# knitic_v2_1.net
KiCad netlist of a schematic drawn in EAGLE
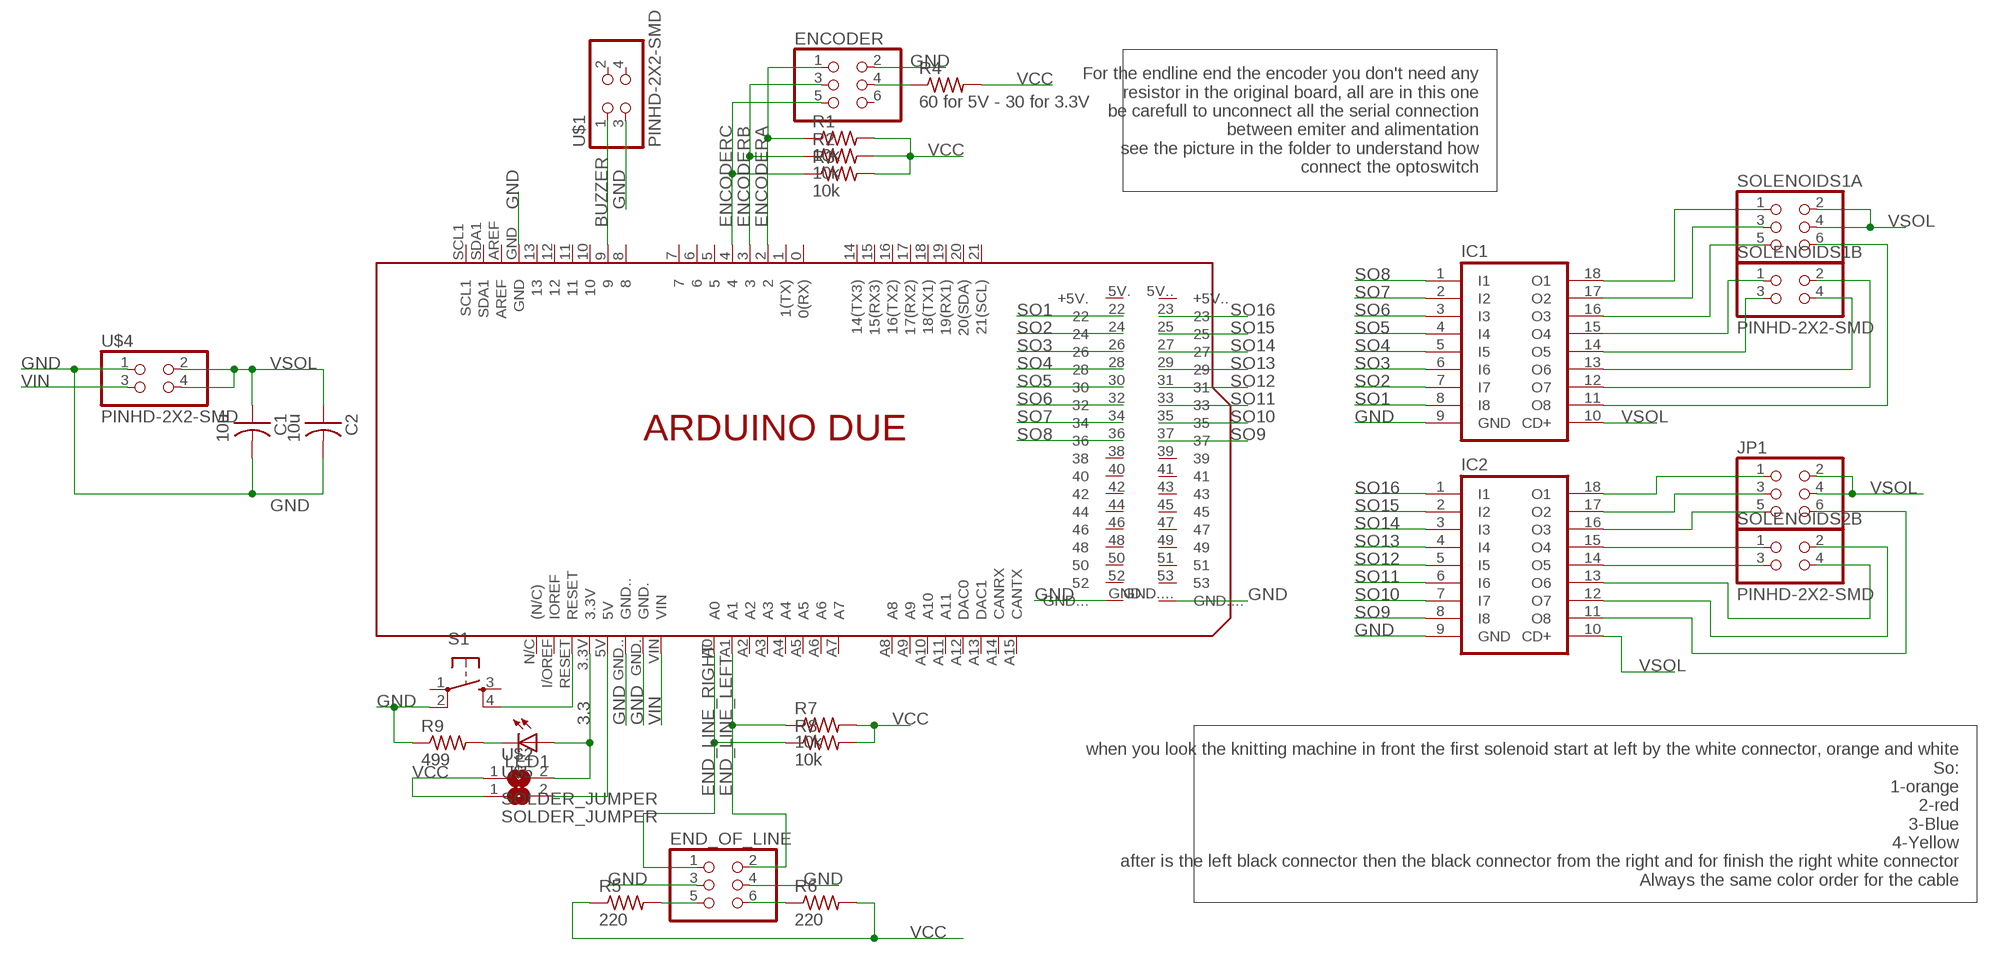
[diagram p0: schematic, sheet 1]

(export (version "E")
  (design (tool "Eeschema 10.0.6"))
  (components
    (comp (ref "C1")
      (value "10u")
      (footprint "eagle-import:C1206FAB")
      (libsource (lib "eagle-import") (part "CAP-US1206FAB"))
    )
    (comp (ref "C2")
      (value "10u")
      (footprint "eagle-import:C1206FAB")
      (libsource (lib "eagle-import") (part "CAP-US1206FAB"))
    )
    (comp (ref "ENCODER")
      (value "PINHD-2X3-SMD")
      (footprint "eagle-import:2X03SMD")
      (libsource (lib "eagle-import") (part "PINHD-2X3-SMD"))
    )
    (comp (ref "END_OF_LINE")
      (value "PINHD-2X3-SMD")
      (footprint "eagle-import:2X03SMD")
      (libsource (lib "eagle-import") (part "PINHD-2X3-SMD"))
    )
    (comp (ref "IC1")
      (value "ULN2803ASO")
      (footprint "eagle-import:SO18W")
      (libsource (lib "eagle-import") (part "ULN2803ASO"))
    )
    (comp (ref "IC2")
      (value "ULN2803ASO")
      (footprint "eagle-import:SO18W")
      (libsource (lib "eagle-import") (part "ULN2803ASO"))
    )
    (comp (ref "JP1")
      (value "PINHD-2X3-SMD")
      (footprint "eagle-import:2X03SMD")
      (libsource (lib "eagle-import") (part "PINHD-2X3-SMD"))
    )
    (comp (ref "LED1")
      (value "LEDSMT1206")
      (footprint "eagle-import:1206")
      (libsource (lib "eagle-import") (part "LEDSMT1206"))
    )
    (comp (ref "PCB1")
      (value "ARDUINO_DUE_MIN")
      (footprint "eagle-import:ARDUINO_DUE_MIN")
      (libsource (lib "eagle-import") (part "ARDUINO_DUE_MIN"))
    )
    (comp (ref "R1")
      (value "10k")
      (footprint "eagle-import:R1206FAB")
      (libsource (lib "eagle-import") (part "RES-US1206FAB"))
    )
    (comp (ref "R2")
      (value "10k")
      (footprint "eagle-import:R1206FAB")
      (libsource (lib "eagle-import") (part "RES-US1206FAB"))
    )
    (comp (ref "R3")
      (value "10k")
      (footprint "eagle-import:R1206FAB")
      (libsource (lib "eagle-import") (part "RES-US1206FAB"))
    )
    (comp (ref "R4")
      (value "60 for 5V - 30 for 3.3V")
      (footprint "eagle-import:R1206FAB")
      (libsource (lib "eagle-import") (part "RES-US1206FAB"))
    )
    (comp (ref "R5")
      (value "220")
      (footprint "eagle-import:R1206FAB")
      (libsource (lib "eagle-import") (part "RES-US1206FAB"))
    )
    (comp (ref "R6")
      (value "220")
      (footprint "eagle-import:R1206FAB")
      (libsource (lib "eagle-import") (part "RES-US1206FAB"))
    )
    (comp (ref "R7")
      (value "10k")
      (footprint "eagle-import:R1206FAB")
      (libsource (lib "eagle-import") (part "RES-US1206FAB"))
    )
    (comp (ref "R8")
      (value "10k")
      (footprint "eagle-import:R1206FAB")
      (libsource (lib "eagle-import") (part "RES-US1206FAB"))
    )
    (comp (ref "R9")
      (value "499")
      (footprint "eagle-import:R1206FAB")
      (libsource (lib "eagle-import") (part "RES-US1206FAB"))
    )
    (comp (ref "S1")
      (value "6MM_SWITCH6MM_SWITCH")
      (footprint "eagle-import:6MM_SWITCH")
      (libsource (lib "eagle-import") (part "6MM_SWITCH6MM_SWITCH"))
    )
    (comp (ref "SOLENOIDS1A")
      (value "PINHD-2X3-SMD")
      (footprint "eagle-import:2X03SMD")
      (libsource (lib "eagle-import") (part "PINHD-2X3-SMD"))
    )
    (comp (ref "SOLENOIDS1B")
      (value "PINHD-2X2-SMD")
      (footprint "eagle-import:2X02SMD")
      (libsource (lib "eagle-import") (part "PINHD-2X2-SMD"))
    )
    (comp (ref "SOLENOIDS2B")
      (value "PINHD-2X2-SMD")
      (footprint "eagle-import:2X02SMD")
      (libsource (lib "eagle-import") (part "PINHD-2X2-SMD"))
    )
    (comp (ref "U$1")
      (value "PINHD-2X2-SMD")
      (footprint "eagle-import:2X02SMD")
      (libsource (lib "eagle-import") (part "PINHD-2X2-SMD"))
    )
    (comp (ref "U$2")
      (value "SOLDER_JUMPER")
      (footprint "eagle-import:SJFAB")
      (libsource (lib "eagle-import") (part "SOLDER_JUMPER"))
    )
    (comp (ref "U$4")
      (value "PINHD-2X2-SMD")
      (footprint "eagle-import:2X02SMD")
      (libsource (lib "eagle-import") (part "PINHD-2X2-SMD"))
    )
    (comp (ref "U$5")
      (value "SOLDER_JUMPER")
      (footprint "eagle-import:SJFAB")
      (libsource (lib "eagle-import") (part "SOLDER_JUMPER"))
    )
  )
  (nets
    (net (code "1") (name "/3.3") (class "Default")
      (node (ref "LED1") (pin "A") (pinfunction "A_A") (pintype "passive"))
      (node (ref "PCB1") (pin "3.3V") (pinfunction "3.3V_3.3V") (pintype "bidirectional"))
      (node (ref "U$2") (pin "2") (pinfunction "2_2") (pintype "passive"))
    )
    (net (code "2") (name "/BUZZER") (class "Default")
      (node (ref "PCB1") (pin "9") (pinfunction "9_9") (pintype "bidirectional"))
      (node (ref "U$1") (pin "1") (pinfunction "1_1") (pintype "passive"))
    )
    (net (code "3") (name "/ENCODERA") (class "Default")
      (node (ref "ENCODER") (pin "1") (pinfunction "1_1") (pintype "passive"))
      (node (ref "PCB1") (pin "2") (pinfunction "2_2") (pintype "bidirectional"))
      (node (ref "R1") (pin "1") (pinfunction "1_1") (pintype "passive"))
    )
    (net (code "4") (name "/ENCODERB") (class "Default")
      (node (ref "ENCODER") (pin "3") (pinfunction "3_3") (pintype "passive"))
      (node (ref "PCB1") (pin "3") (pinfunction "3_3") (pintype "bidirectional"))
      (node (ref "R2") (pin "1") (pinfunction "1_1") (pintype "passive"))
    )
    (net (code "5") (name "/ENCODERC") (class "Default")
      (node (ref "ENCODER") (pin "5") (pinfunction "5_5") (pintype "passive"))
      (node (ref "PCB1") (pin "4") (pinfunction "4_4") (pintype "bidirectional"))
      (node (ref "R3") (pin "1") (pinfunction "1_1") (pintype "passive"))
    )
    (net (code "6") (name "/END_LINE_LEFT") (class "Default")
      (node (ref "END_OF_LINE") (pin "2") (pinfunction "2_2") (pintype "passive"))
      (node (ref "PCB1") (pin "A1") (pinfunction "A1_A1") (pintype "bidirectional"))
      (node (ref "R7") (pin "1") (pinfunction "1_1") (pintype "passive"))
    )
    (net (code "7") (name "/END_LINE_RIGHT") (class "Default")
      (node (ref "END_OF_LINE") (pin "1") (pinfunction "1_1") (pintype "passive"))
      (node (ref "PCB1") (pin "A0") (pinfunction "A0_A0") (pintype "bidirectional"))
      (node (ref "R8") (pin "1") (pinfunction "1_1") (pintype "passive"))
    )
    (net (code "8") (name "/GND") (class "Default")
      (node (ref "C1") (pin "2") (pinfunction "2_2") (pintype "passive"))
      (node (ref "C2") (pin "2") (pinfunction "2_2") (pintype "passive"))
      (node (ref "ENCODER") (pin "2") (pinfunction "2_2") (pintype "passive"))
      (node (ref "END_OF_LINE") (pin "3") (pinfunction "3_3") (pintype "passive"))
      (node (ref "END_OF_LINE") (pin "4") (pinfunction "4_4") (pintype "passive"))
      (node (ref "IC1") (pin "9") (pinfunction "GND_9") (pintype "power_in"))
      (node (ref "IC2") (pin "9") (pinfunction "GND_9") (pintype "power_in"))
      (node (ref "PCB1") (pin "GND") (pinfunction "GND_GND") (pintype "bidirectional"))
      (node (ref "PCB1") (pin "GND.") (pinfunction "GND._GND.") (pintype "bidirectional"))
      (node (ref "PCB1") (pin "GND..") (pinfunction "GND.._GND..") (pintype "bidirectional"))
      (node (ref "R9") (pin "1") (pinfunction "1_1") (pintype "passive"))
      (node (ref "S1") (pin "2") (pinfunction "P1_2") (pintype "passive"))
      (node (ref "U$1") (pin "3") (pinfunction "3_3") (pintype "passive"))
      (node (ref "U$4") (pin "1") (pinfunction "1_1") (pintype "passive"))
    )
    (net (code "9") (name "/SO1") (class "Default")
      (node (ref "IC1") (pin "8") (pinfunction "I8_8") (pintype "input"))
      (node (ref "PCB1") (pin "22") (pinfunction "22_22") (pintype "bidirectional"))
    )
    (net (code "10") (name "/SO2") (class "Default")
      (node (ref "IC1") (pin "7") (pinfunction "I7_7") (pintype "input"))
      (node (ref "PCB1") (pin "24") (pinfunction "24_24") (pintype "bidirectional"))
    )
    (net (code "11") (name "/SO3") (class "Default")
      (node (ref "IC1") (pin "6") (pinfunction "I6_6") (pintype "input"))
      (node (ref "PCB1") (pin "26") (pinfunction "26_26") (pintype "bidirectional"))
    )
    (net (code "12") (name "/SO4") (class "Default")
      (node (ref "IC1") (pin "5") (pinfunction "I5_5") (pintype "input"))
      (node (ref "PCB1") (pin "28") (pinfunction "28_28") (pintype "bidirectional"))
    )
    (net (code "13") (name "/SO5") (class "Default")
      (node (ref "IC1") (pin "4") (pinfunction "I4_4") (pintype "input"))
      (node (ref "PCB1") (pin "30") (pinfunction "30_30") (pintype "bidirectional"))
    )
    (net (code "14") (name "/SO6") (class "Default")
      (node (ref "IC1") (pin "3") (pinfunction "I3_3") (pintype "input"))
      (node (ref "PCB1") (pin "32") (pinfunction "32_32") (pintype "bidirectional"))
    )
    (net (code "15") (name "/SO7") (class "Default")
      (node (ref "IC1") (pin "2") (pinfunction "I2_2") (pintype "input"))
      (node (ref "PCB1") (pin "34") (pinfunction "34_34") (pintype "bidirectional"))
    )
    (net (code "16") (name "/SO8") (class "Default")
      (node (ref "IC1") (pin "1") (pinfunction "I1_1") (pintype "input"))
      (node (ref "PCB1") (pin "36") (pinfunction "36_36") (pintype "bidirectional"))
    )
    (net (code "17") (name "/SO9") (class "Default")
      (node (ref "IC2") (pin "8") (pinfunction "I8_8") (pintype "input"))
      (node (ref "PCB1") (pin "37") (pinfunction "37_37") (pintype "bidirectional"))
    )
    (net (code "18") (name "/SO10") (class "Default")
      (node (ref "IC2") (pin "7") (pinfunction "I7_7") (pintype "input"))
      (node (ref "PCB1") (pin "35") (pinfunction "35_35") (pintype "bidirectional"))
    )
    (net (code "19") (name "/SO11") (class "Default")
      (node (ref "IC2") (pin "6") (pinfunction "I6_6") (pintype "input"))
      (node (ref "PCB1") (pin "33") (pinfunction "33_33") (pintype "bidirectional"))
    )
    (net (code "20") (name "/SO12") (class "Default")
      (node (ref "IC2") (pin "5") (pinfunction "I5_5") (pintype "input"))
      (node (ref "PCB1") (pin "31") (pinfunction "31_31") (pintype "bidirectional"))
    )
    (net (code "21") (name "/SO13") (class "Default")
      (node (ref "IC2") (pin "4") (pinfunction "I4_4") (pintype "input"))
      (node (ref "PCB1") (pin "29") (pinfunction "29_29") (pintype "bidirectional"))
    )
    (net (code "22") (name "/SO14") (class "Default")
      (node (ref "IC2") (pin "3") (pinfunction "I3_3") (pintype "input"))
      (node (ref "PCB1") (pin "27") (pinfunction "27_27") (pintype "bidirectional"))
    )
    (net (code "23") (name "/SO15") (class "Default")
      (node (ref "IC2") (pin "2") (pinfunction "I2_2") (pintype "input"))
      (node (ref "PCB1") (pin "25") (pinfunction "25_25") (pintype "bidirectional"))
    )
    (net (code "24") (name "/SO16") (class "Default")
      (node (ref "IC2") (pin "1") (pinfunction "I1_1") (pintype "input"))
      (node (ref "PCB1") (pin "23") (pinfunction "23_23") (pintype "bidirectional"))
    )
    (net (code "25") (name "/VCC") (class "Default")
      (node (ref "R1") (pin "2") (pinfunction "2_2") (pintype "passive"))
      (node (ref "R2") (pin "2") (pinfunction "2_2") (pintype "passive"))
      (node (ref "R3") (pin "2") (pinfunction "2_2") (pintype "passive"))
      (node (ref "R4") (pin "2") (pinfunction "2_2") (pintype "passive"))
      (node (ref "R5") (pin "1") (pinfunction "1_1") (pintype "passive"))
      (node (ref "R6") (pin "2") (pinfunction "2_2") (pintype "passive"))
      (node (ref "R7") (pin "2") (pinfunction "2_2") (pintype "passive"))
      (node (ref "R8") (pin "2") (pinfunction "2_2") (pintype "passive"))
      (node (ref "U$2") (pin "1") (pinfunction "1_1") (pintype "passive"))
      (node (ref "U$5") (pin "1") (pinfunction "1_1") (pintype "passive"))
    )
    (net (code "26") (name "/VIN") (class "Default")
      (node (ref "PCB1") (pin "VIN") (pinfunction "VIN_VIN") (pintype "bidirectional"))
      (node (ref "U$4") (pin "3") (pinfunction "3_3") (pintype "passive"))
    )
    (net (code "27") (name "/VSOL") (class "Default")
      (node (ref "C1") (pin "1") (pinfunction "1_1") (pintype "passive"))
      (node (ref "C2") (pin "1") (pinfunction "1_1") (pintype "passive"))
      (node (ref "IC1") (pin "10") (pinfunction "CD+_10") (pintype "passive"))
      (node (ref "IC2") (pin "10") (pinfunction "CD+_10") (pintype "passive"))
      (node (ref "JP1") (pin "2") (pinfunction "2_2") (pintype "passive"))
      (node (ref "JP1") (pin "4") (pinfunction "4_4") (pintype "passive"))
      (node (ref "SOLENOIDS1A") (pin "2") (pinfunction "2_2") (pintype "passive"))
      (node (ref "SOLENOIDS1A") (pin "4") (pinfunction "4_4") (pintype "passive"))
      (node (ref "U$4") (pin "2") (pinfunction "2_2") (pintype "passive"))
      (node (ref "U$4") (pin "4") (pinfunction "4_4") (pintype "passive"))
    )
    (net (code "28") (name "Net-(ENCODER-Pad4)") (class "Default")
      (node (ref "ENCODER") (pin "4") (pinfunction "4_4") (pintype "passive"))
      (node (ref "R4") (pin "1") (pinfunction "1_1") (pintype "passive"))
    )
    (net (code "29") (name "Net-(END_OF_LINE-Pad5)") (class "Default")
      (node (ref "END_OF_LINE") (pin "5") (pinfunction "5_5") (pintype "passive"))
      (node (ref "R5") (pin "2") (pinfunction "2_2") (pintype "passive"))
    )
    (net (code "30") (name "Net-(END_OF_LINE-Pad6)") (class "Default")
      (node (ref "END_OF_LINE") (pin "6") (pinfunction "6_6") (pintype "passive"))
      (node (ref "R6") (pin "1") (pinfunction "1_1") (pintype "passive"))
    )
    (net (code "31") (name "Net-(IC1-O1)") (class "Default")
      (node (ref "IC1") (pin "18") (pinfunction "O1_18") (pintype "open_collector"))
      (node (ref "SOLENOIDS1A") (pin "1") (pinfunction "1_1") (pintype "passive"))
    )
    (net (code "32") (name "Net-(IC1-O2)") (class "Default")
      (node (ref "IC1") (pin "17") (pinfunction "O2_17") (pintype "open_collector"))
      (node (ref "SOLENOIDS1A") (pin "3") (pinfunction "3_3") (pintype "passive"))
    )
    (net (code "33") (name "Net-(IC1-O3)") (class "Default")
      (node (ref "IC1") (pin "16") (pinfunction "O3_16") (pintype "open_collector"))
      (node (ref "SOLENOIDS1A") (pin "5") (pinfunction "5_5") (pintype "passive"))
    )
    (net (code "34") (name "Net-(IC1-O4)") (class "Default")
      (node (ref "IC1") (pin "15") (pinfunction "O4_15") (pintype "open_collector"))
      (node (ref "SOLENOIDS1B") (pin "1") (pinfunction "1_1") (pintype "passive"))
    )
    (net (code "35") (name "Net-(IC1-O5)") (class "Default")
      (node (ref "IC1") (pin "14") (pinfunction "O5_14") (pintype "open_collector"))
      (node (ref "SOLENOIDS1B") (pin "3") (pinfunction "3_3") (pintype "passive"))
    )
    (net (code "36") (name "Net-(IC1-O6)") (class "Default")
      (node (ref "IC1") (pin "13") (pinfunction "O6_13") (pintype "open_collector"))
      (node (ref "SOLENOIDS1B") (pin "4") (pinfunction "4_4") (pintype "passive"))
    )
    (net (code "37") (name "Net-(IC1-O7)") (class "Default")
      (node (ref "IC1") (pin "12") (pinfunction "O7_12") (pintype "open_collector"))
      (node (ref "SOLENOIDS1B") (pin "2") (pinfunction "2_2") (pintype "passive"))
    )
    (net (code "38") (name "Net-(IC1-O8)") (class "Default")
      (node (ref "IC1") (pin "11") (pinfunction "O8_11") (pintype "open_collector"))
      (node (ref "SOLENOIDS1A") (pin "6") (pinfunction "6_6") (pintype "passive"))
    )
    (net (code "39") (name "Net-(IC2-O1)") (class "Default")
      (node (ref "IC2") (pin "18") (pinfunction "O1_18") (pintype "open_collector"))
      (node (ref "JP1") (pin "1") (pinfunction "1_1") (pintype "passive"))
    )
    (net (code "40") (name "Net-(IC2-O2)") (class "Default")
      (node (ref "IC2") (pin "17") (pinfunction "O2_17") (pintype "open_collector"))
      (node (ref "JP1") (pin "3") (pinfunction "3_3") (pintype "passive"))
    )
    (net (code "41") (name "Net-(IC2-O3)") (class "Default")
      (node (ref "IC2") (pin "16") (pinfunction "O3_16") (pintype "open_collector"))
      (node (ref "JP1") (pin "5") (pinfunction "5_5") (pintype "passive"))
    )
    (net (code "42") (name "Net-(IC2-O4)") (class "Default")
      (node (ref "IC2") (pin "15") (pinfunction "O4_15") (pintype "open_collector"))
      (node (ref "SOLENOIDS2B") (pin "1") (pinfunction "1_1") (pintype "passive"))
    )
    (net (code "43") (name "Net-(IC2-O5)") (class "Default")
      (node (ref "IC2") (pin "14") (pinfunction "O5_14") (pintype "open_collector"))
      (node (ref "SOLENOIDS2B") (pin "3") (pinfunction "3_3") (pintype "passive"))
    )
    (net (code "44") (name "Net-(IC2-O6)") (class "Default")
      (node (ref "IC2") (pin "13") (pinfunction "O6_13") (pintype "open_collector"))
      (node (ref "SOLENOIDS2B") (pin "4") (pinfunction "4_4") (pintype "passive"))
    )
    (net (code "45") (name "Net-(IC2-O7)") (class "Default")
      (node (ref "IC2") (pin "12") (pinfunction "O7_12") (pintype "open_collector"))
      (node (ref "SOLENOIDS2B") (pin "2") (pinfunction "2_2") (pintype "passive"))
    )
    (net (code "46") (name "Net-(IC2-O8)") (class "Default")
      (node (ref "IC2") (pin "11") (pinfunction "O8_11") (pintype "open_collector"))
      (node (ref "JP1") (pin "6") (pinfunction "6_6") (pintype "passive"))
    )
    (net (code "47") (name "Net-(LED1-PadC)") (class "Default")
      (node (ref "LED1") (pin "C") (pinfunction "C_C") (pintype "passive"))
      (node (ref "R9") (pin "2") (pinfunction "2_2") (pintype "passive"))
    )
    (net (code "48") (name "Net-(PCB1-Pad5V)") (class "Default")
      (node (ref "PCB1") (pin "5V") (pinfunction "5V_5V") (pintype "bidirectional"))
      (node (ref "U$5") (pin "2") (pinfunction "2_2") (pintype "passive"))
    )
    (net (code "49") (name "Net-(S1-S1)") (class "Default")
      (node (ref "PCB1") (pin "RESET") (pinfunction "RESET_RESET") (pintype "bidirectional"))
      (node (ref "S1") (pin "4") (pinfunction "S1_4") (pintype "passive"))
    )
    (net (code "50") (name "unconnected-(ENCODER-Pad6)") (class "Default")
      (node (ref "ENCODER") (pin "6") (pinfunction "6_6") (pintype "passive"))
    )
    (net (code "51") (name "unconnected-(PCB1-(N{slash}C)-PadN{slash}C)") (class "Default")
      (node (ref "PCB1") (pin "N/C") (pinfunction "(N/C)_N/C") (pintype "bidirectional"))
    )
    (net (code "52") (name "unconnected-(PCB1-+5V.-Pad5V.)") (class "Default")
      (node (ref "PCB1") (pin "5V.") (pinfunction "+5V._5V.") (pintype "bidirectional"))
    )
    (net (code "53") (name "unconnected-(PCB1-+5V..-Pad5V..)") (class "Default")
      (node (ref "PCB1") (pin "5V..") (pinfunction "+5V.._5V..") (pintype "bidirectional"))
    )
    (net (code "54") (name "unconnected-(PCB1-0(RX)-Pad0)") (class "Default")
      (node (ref "PCB1") (pin "0") (pinfunction "0(RX)_0") (pintype "bidirectional"))
    )
    (net (code "55") (name "unconnected-(PCB1-1(TX)-Pad1)") (class "Default")
      (node (ref "PCB1") (pin "1") (pinfunction "1(TX)_1") (pintype "bidirectional"))
    )
    (net (code "56") (name "unconnected-(PCB1-14(TX3)-Pad14)") (class "Default")
      (node (ref "PCB1") (pin "14") (pinfunction "14(TX3)_14") (pintype "bidirectional"))
    )
    (net (code "57") (name "unconnected-(PCB1-15(RX3)-Pad15)") (class "Default")
      (node (ref "PCB1") (pin "15") (pinfunction "15(RX3)_15") (pintype "bidirectional"))
    )
    (net (code "58") (name "unconnected-(PCB1-16(TX2)-Pad16)") (class "Default")
      (node (ref "PCB1") (pin "16") (pinfunction "16(TX2)_16") (pintype "bidirectional"))
    )
    (net (code "59") (name "unconnected-(PCB1-17(RX2)-Pad17)") (class "Default")
      (node (ref "PCB1") (pin "17") (pinfunction "17(RX2)_17") (pintype "bidirectional"))
    )
    (net (code "60") (name "unconnected-(PCB1-18(TX1)-Pad18)") (class "Default")
      (node (ref "PCB1") (pin "18") (pinfunction "18(TX1)_18") (pintype "bidirectional"))
    )
    (net (code "61") (name "unconnected-(PCB1-19(RX1)-Pad19)") (class "Default")
      (node (ref "PCB1") (pin "19") (pinfunction "19(RX1)_19") (pintype "bidirectional"))
    )
    (net (code "62") (name "unconnected-(PCB1-20(SDA)-Pad20)") (class "Default")
      (node (ref "PCB1") (pin "20") (pinfunction "20(SDA)_20") (pintype "bidirectional"))
    )
    (net (code "63") (name "unconnected-(PCB1-21(SCL)-Pad21)") (class "Default")
      (node (ref "PCB1") (pin "21") (pinfunction "21(SCL)_21") (pintype "bidirectional"))
    )
    (net (code "64") (name "unconnected-(PCB1-CANRX-PadA14)") (class "Default")
      (node (ref "PCB1") (pin "A14") (pinfunction "CANRX_A14") (pintype "bidirectional"))
    )
    (net (code "65") (name "unconnected-(PCB1-CANTX-PadA15)") (class "Default")
      (node (ref "PCB1") (pin "A15") (pinfunction "CANTX_A15") (pintype "bidirectional"))
    )
    (net (code "66") (name "unconnected-(PCB1-DAC0-PadA12)") (class "Default")
      (node (ref "PCB1") (pin "A12") (pinfunction "DAC0_A12") (pintype "bidirectional"))
    )
    (net (code "67") (name "unconnected-(PCB1-DAC1-PadA13)") (class "Default")
      (node (ref "PCB1") (pin "A13") (pinfunction "DAC1_A13") (pintype "bidirectional"))
    )
    (net (code "68") (name "unconnected-(PCB1-IOREF-PadI{slash}OREF)") (class "Default")
      (node (ref "PCB1") (pin "I/OREF") (pinfunction "IOREF_I/OREF") (pintype "bidirectional"))
    )
    (net (code "69") (name "unconnected-(PCB1-Pad5)") (class "Default")
      (node (ref "PCB1") (pin "5") (pinfunction "5_5") (pintype "bidirectional"))
    )
    (net (code "70") (name "unconnected-(PCB1-Pad6)") (class "Default")
      (node (ref "PCB1") (pin "6") (pinfunction "6_6") (pintype "bidirectional"))
    )
    (net (code "71") (name "unconnected-(PCB1-Pad7)") (class "Default")
      (node (ref "PCB1") (pin "7") (pinfunction "7_7") (pintype "bidirectional"))
    )
    (net (code "72") (name "unconnected-(PCB1-Pad8)") (class "Default")
      (node (ref "PCB1") (pin "8") (pinfunction "8_8") (pintype "bidirectional"))
    )
    (net (code "73") (name "unconnected-(PCB1-Pad10)") (class "Default")
      (node (ref "PCB1") (pin "10") (pinfunction "10_10") (pintype "bidirectional"))
    )
    (net (code "74") (name "unconnected-(PCB1-Pad11)") (class "Default")
      (node (ref "PCB1") (pin "11") (pinfunction "11_11") (pintype "bidirectional"))
    )
    (net (code "75") (name "unconnected-(PCB1-Pad12)") (class "Default")
      (node (ref "PCB1") (pin "12") (pinfunction "12_12") (pintype "bidirectional"))
    )
    (net (code "76") (name "unconnected-(PCB1-Pad13)") (class "Default")
      (node (ref "PCB1") (pin "13") (pinfunction "13_13") (pintype "bidirectional"))
    )
    (net (code "77") (name "unconnected-(PCB1-Pad38)") (class "Default")
      (node (ref "PCB1") (pin "38") (pinfunction "38_38") (pintype "bidirectional"))
    )
    (net (code "78") (name "unconnected-(PCB1-Pad39)") (class "Default")
      (node (ref "PCB1") (pin "39") (pinfunction "39_39") (pintype "bidirectional"))
    )
    (net (code "79") (name "unconnected-(PCB1-Pad40)") (class "Default")
      (node (ref "PCB1") (pin "40") (pinfunction "40_40") (pintype "bidirectional"))
    )
    (net (code "80") (name "unconnected-(PCB1-Pad41)") (class "Default")
      (node (ref "PCB1") (pin "41") (pinfunction "41_41") (pintype "bidirectional"))
    )
    (net (code "81") (name "unconnected-(PCB1-Pad42)") (class "Default")
      (node (ref "PCB1") (pin "42") (pinfunction "42_42") (pintype "bidirectional"))
    )
    (net (code "82") (name "unconnected-(PCB1-Pad43)") (class "Default")
      (node (ref "PCB1") (pin "43") (pinfunction "43_43") (pintype "bidirectional"))
    )
    (net (code "83") (name "unconnected-(PCB1-Pad44)") (class "Default")
      (node (ref "PCB1") (pin "44") (pinfunction "44_44") (pintype "bidirectional"))
    )
    (net (code "84") (name "unconnected-(PCB1-Pad45)") (class "Default")
      (node (ref "PCB1") (pin "45") (pinfunction "45_45") (pintype "bidirectional"))
    )
    (net (code "85") (name "unconnected-(PCB1-Pad46)") (class "Default")
      (node (ref "PCB1") (pin "46") (pinfunction "46_46") (pintype "bidirectional"))
    )
    (net (code "86") (name "unconnected-(PCB1-Pad47)") (class "Default")
      (node (ref "PCB1") (pin "47") (pinfunction "47_47") (pintype "bidirectional"))
    )
    (net (code "87") (name "unconnected-(PCB1-Pad48)") (class "Default")
      (node (ref "PCB1") (pin "48") (pinfunction "48_48") (pintype "bidirectional"))
    )
    (net (code "88") (name "unconnected-(PCB1-Pad49)") (class "Default")
      (node (ref "PCB1") (pin "49") (pinfunction "49_49") (pintype "bidirectional"))
    )
    (net (code "89") (name "unconnected-(PCB1-Pad50)") (class "Default")
      (node (ref "PCB1") (pin "50") (pinfunction "50_50") (pintype "bidirectional"))
    )
    (net (code "90") (name "unconnected-(PCB1-Pad51)") (class "Default")
      (node (ref "PCB1") (pin "51") (pinfunction "51_51") (pintype "bidirectional"))
    )
    (net (code "91") (name "unconnected-(PCB1-Pad52)") (class "Default")
      (node (ref "PCB1") (pin "52") (pinfunction "52_52") (pintype "bidirectional"))
    )
    (net (code "92") (name "unconnected-(PCB1-Pad53)") (class "Default")
      (node (ref "PCB1") (pin "53") (pinfunction "53_53") (pintype "bidirectional"))
    )
    (net (code "93") (name "unconnected-(PCB1-PadA2)") (class "Default")
      (node (ref "PCB1") (pin "A2") (pinfunction "A2_A2") (pintype "bidirectional"))
    )
    (net (code "94") (name "unconnected-(PCB1-PadA3)") (class "Default")
      (node (ref "PCB1") (pin "A3") (pinfunction "A3_A3") (pintype "bidirectional"))
    )
    (net (code "95") (name "unconnected-(PCB1-PadA4)") (class "Default")
      (node (ref "PCB1") (pin "A4") (pinfunction "A4_A4") (pintype "bidirectional"))
    )
    (net (code "96") (name "unconnected-(PCB1-PadA5)") (class "Default")
      (node (ref "PCB1") (pin "A5") (pinfunction "A5_A5") (pintype "bidirectional"))
    )
    (net (code "97") (name "unconnected-(PCB1-PadA6)") (class "Default")
      (node (ref "PCB1") (pin "A6") (pinfunction "A6_A6") (pintype "bidirectional"))
    )
    (net (code "98") (name "unconnected-(PCB1-PadA7)") (class "Default")
      (node (ref "PCB1") (pin "A7") (pinfunction "A7_A7") (pintype "bidirectional"))
    )
    (net (code "99") (name "unconnected-(PCB1-PadA8)") (class "Default")
      (node (ref "PCB1") (pin "A8") (pinfunction "A8_A8") (pintype "bidirectional"))
    )
    (net (code "100") (name "unconnected-(PCB1-PadA9)") (class "Default")
      (node (ref "PCB1") (pin "A9") (pinfunction "A9_A9") (pintype "bidirectional"))
    )
    (net (code "101") (name "unconnected-(PCB1-PadA10)") (class "Default")
      (node (ref "PCB1") (pin "A10") (pinfunction "A10_A10") (pintype "bidirectional"))
    )
    (net (code "102") (name "unconnected-(PCB1-PadA11)") (class "Default")
      (node (ref "PCB1") (pin "A11") (pinfunction "A11_A11") (pintype "bidirectional"))
    )
    (net (code "103") (name "unconnected-(PCB1-PadAREF)") (class "Default")
      (node (ref "PCB1") (pin "AREF") (pinfunction "AREF_AREF") (pintype "bidirectional"))
    )
    (net (code "104") (name "unconnected-(PCB1-PadGND...)") (class "Default")
      (node (ref "PCB1") (pin "GND...") (pinfunction "GND..._GND...") (pintype "bidirectional"))
    )
    (net (code "105") (name "unconnected-(PCB1-PadGND....)") (class "Default")
      (node (ref "PCB1") (pin "GND....") (pinfunction "GND...._GND....") (pintype "bidirectional"))
    )
    (net (code "106") (name "unconnected-(PCB1-PadSCL1)") (class "Default")
      (node (ref "PCB1") (pin "SCL1") (pinfunction "SCL1_SCL1") (pintype "bidirectional"))
    )
    (net (code "107") (name "unconnected-(PCB1-PadSDA1)") (class "Default")
      (node (ref "PCB1") (pin "SDA1") (pinfunction "SDA1_SDA1") (pintype "bidirectional"))
    )
    (net (code "108") (name "unconnected-(S1-P-Pad1)") (class "Default")
      (node (ref "S1") (pin "1") (pinfunction "P_1") (pintype "passive"))
    )
    (net (code "109") (name "unconnected-(S1-S-Pad3)") (class "Default")
      (node (ref "S1") (pin "3") (pinfunction "S_3") (pintype "passive"))
    )
    (net (code "110") (name "unconnected-(U$1-Pad2)") (class "Default")
      (node (ref "U$1") (pin "2") (pinfunction "2_2") (pintype "passive"))
    )
    (net (code "111") (name "unconnected-(U$1-Pad4)") (class "Default")
      (node (ref "U$1") (pin "4") (pinfunction "4_4") (pintype "passive"))
    )
  )
)
